# Module_SOSI_OS5000_datalogger.net
KiCad netlist of a schematic drawn in EAGLE
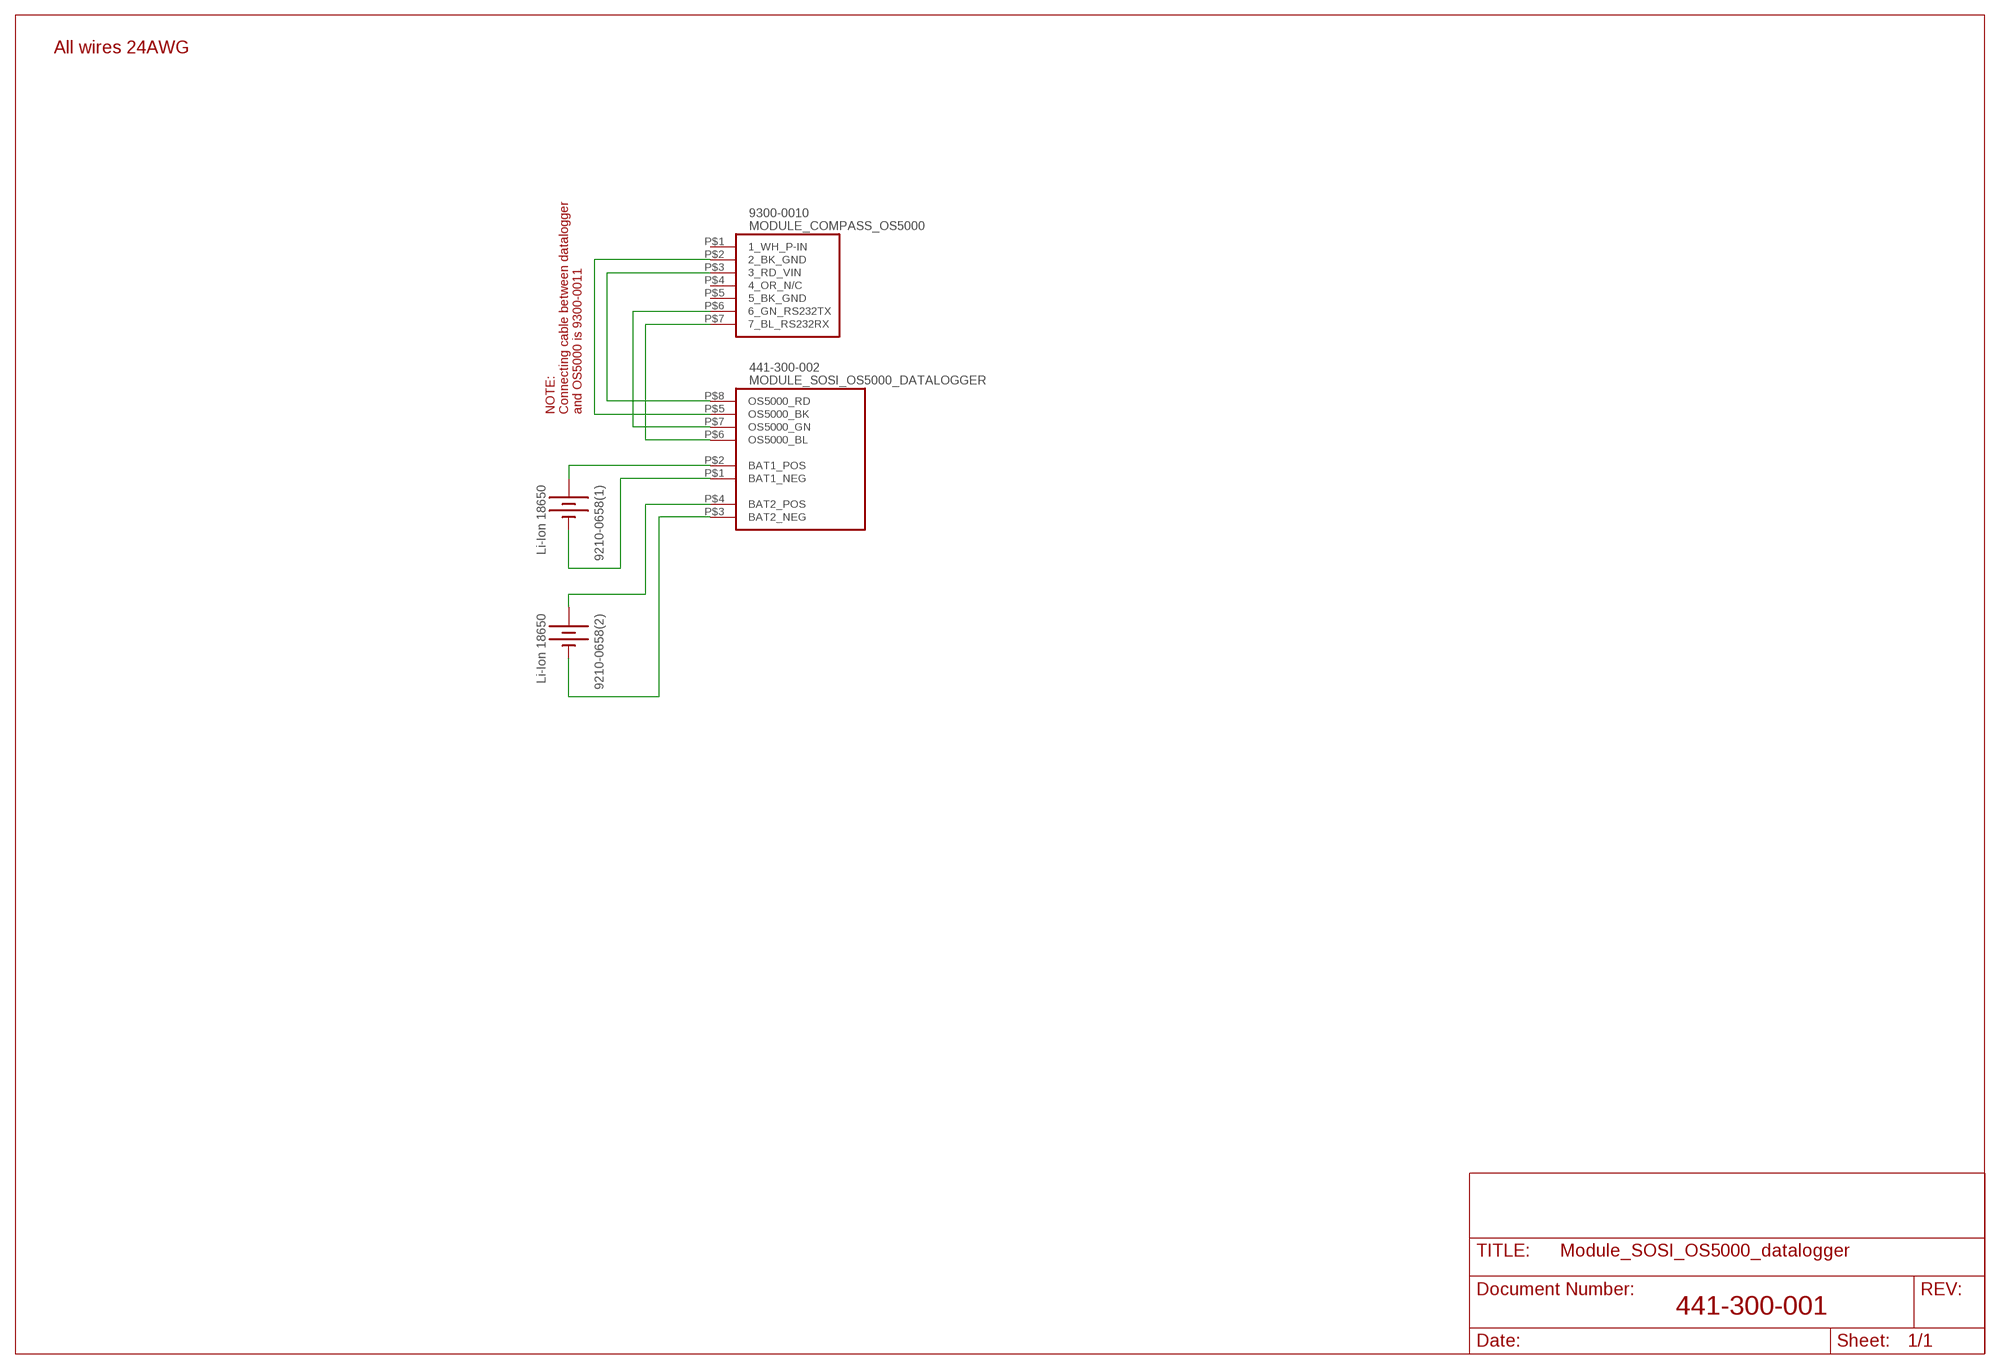
[diagram p0: schematic, sheet 1]

(export (version "E")
  (design (tool "Eeschema 10.0.6"))
  (components
    (comp (ref "441-300-002")
      (value "MODULE_SOSI_OS5000_DATALOGGER")
      (footprint "eagle-import:BOGUS")
      (libsource (lib "eagle-import") (part "MODULE_SOSI_OS5000_DATALOGGER"))
    )
    (comp (ref "9210-0658(1)")
      (value "Li-Ion 18650")
      (footprint "eagle-import:BOGUS")
      (libsource (lib "eagle-import") (part "BATTERY"))
    )
    (comp (ref "9210-0658(2)")
      (value "Li-Ion 18650")
      (footprint "eagle-import:BOGUS")
      (libsource (lib "eagle-import") (part "BATTERY"))
    )
    (comp (ref "9300-0010")
      (value "MODULE_COMPASS_OS5000")
      (footprint "eagle-import:BOGUS")
      (libsource (lib "eagle-import") (part "MODULE_COMPASS_OS5000"))
    )
  )
  (nets
    (net (code "1") (name "Net-(441-300-002-BAT1_NEG)") (class "Default")
      (node (ref "441-300-002") (pin "P$1") (pinfunction "BAT1_NEG_P$1") (pintype "bidirectional"))
      (node (ref "9210-0658(1)") (pin "P$2") (pinfunction "-_P$2") (pintype "power_in"))
    )
    (net (code "2") (name "Net-(441-300-002-BAT1_POS)") (class "Default")
      (node (ref "441-300-002") (pin "P$2") (pinfunction "BAT1_POS_P$2") (pintype "bidirectional"))
      (node (ref "9210-0658(1)") (pin "P$1") (pinfunction "+_P$1") (pintype "power_in"))
    )
    (net (code "3") (name "Net-(441-300-002-BAT2_NEG)") (class "Default")
      (node (ref "441-300-002") (pin "P$3") (pinfunction "BAT2_NEG_P$3") (pintype "bidirectional"))
      (node (ref "9210-0658(2)") (pin "P$2") (pinfunction "-_P$2") (pintype "power_in"))
    )
    (net (code "4") (name "Net-(441-300-002-BAT2_POS)") (class "Default")
      (node (ref "441-300-002") (pin "P$4") (pinfunction "BAT2_POS_P$4") (pintype "bidirectional"))
      (node (ref "9210-0658(2)") (pin "P$1") (pinfunction "+_P$1") (pintype "power_in"))
    )
    (net (code "5") (name "Net-(441-300-002-OS5000_BK)") (class "Default")
      (node (ref "441-300-002") (pin "P$5") (pinfunction "OS5000_BK_P$5") (pintype "bidirectional"))
      (node (ref "9300-0010") (pin "P$2") (pinfunction "2_BK_GND_P$2") (pintype "bidirectional"))
    )
    (net (code "6") (name "Net-(441-300-002-OS5000_BL)") (class "Default")
      (node (ref "441-300-002") (pin "P$6") (pinfunction "OS5000_BL_P$6") (pintype "bidirectional"))
      (node (ref "9300-0010") (pin "P$7") (pinfunction "7_BL_RS232RX_P$7") (pintype "bidirectional"))
    )
    (net (code "7") (name "Net-(441-300-002-OS5000_GN)") (class "Default")
      (node (ref "441-300-002") (pin "P$7") (pinfunction "OS5000_GN_P$7") (pintype "bidirectional"))
      (node (ref "9300-0010") (pin "P$6") (pinfunction "6_GN_RS232TX_P$6") (pintype "bidirectional"))
    )
    (net (code "8") (name "Net-(441-300-002-OS5000_RD)") (class "Default")
      (node (ref "441-300-002") (pin "P$8") (pinfunction "OS5000_RD_P$8") (pintype "bidirectional"))
      (node (ref "9300-0010") (pin "P$3") (pinfunction "3_RD_VIN_P$3") (pintype "bidirectional"))
    )
    (net (code "9") (name "unconnected-(9300-0010-1_WH_P-IN-PadP$1)") (class "Default")
      (node (ref "9300-0010") (pin "P$1") (pinfunction "1_WH_P-IN_P$1") (pintype "bidirectional"))
    )
    (net (code "10") (name "unconnected-(9300-0010-4_OR_N{slash}C-PadP$4)") (class "Default")
      (node (ref "9300-0010") (pin "P$4") (pinfunction "4_OR_N/C_P$4") (pintype "bidirectional"))
    )
    (net (code "11") (name "unconnected-(9300-0010-5_BK_GND-PadP$5)") (class "Default")
      (node (ref "9300-0010") (pin "P$5") (pinfunction "5_BK_GND_P$5") (pintype "bidirectional"))
    )
  )
)
